# scheme.net
KiCad netlist of a schematic drawn in Altium Designer
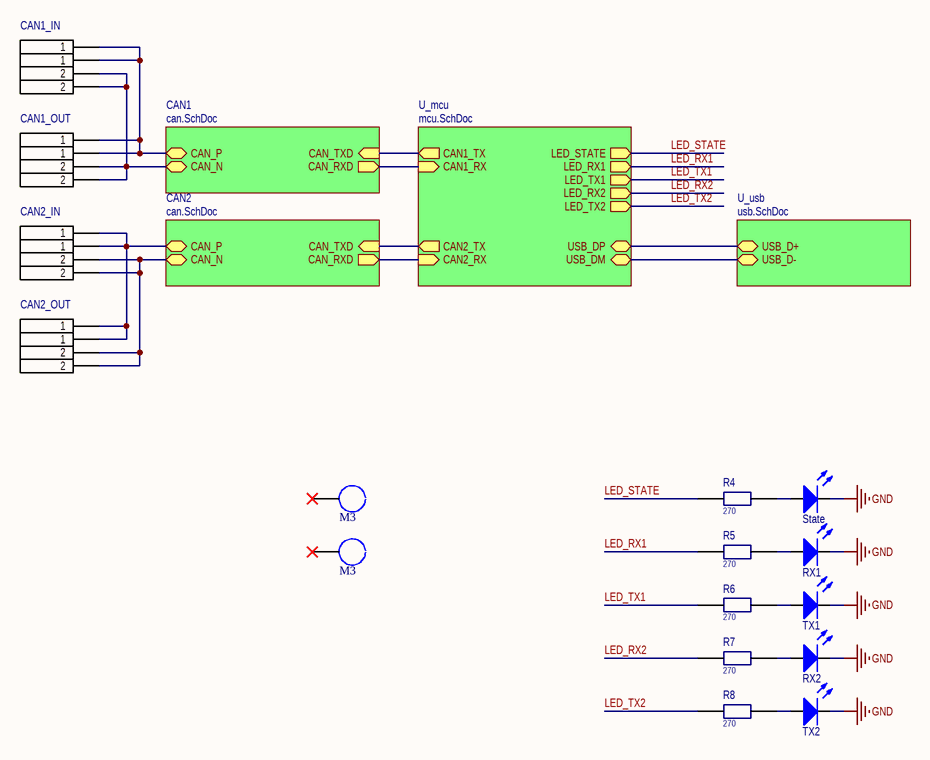
[diagram p0: scheme.SchDoc]

(export (version "E")
  (design (tool "Eeschema 10.0.6"))
  (components
    (comp (ref "*1") (value "M3") (footprint "M3") (libsource (lib "connectors_socets") (part "M3")))
    (comp (ref "*2") (value "M3") (footprint "M3") (libsource (lib "connectors_socets") (part "M3")))
    (comp (ref "CAN1_IN")
      (value "TBLH10-350-02BK")
      (footprint "CUI_TBLH10-350-02BK")
      (fields (field (name "ALTERNATIVE PART") "JILN JL212R-35002B01"))
      (libsource (lib "connectors_socets") (part "TBLH10-350-02BK"))
    )
    (comp (ref "CAN1_OUT")
      (value "TBLH10-350-02BK")
      (footprint "CUI_TBLH10-350-02BK")
      (libsource (lib "connectors_socets") (part "TBLH10-350-02BK"))
    )
    (comp (ref "CAN2_IN")
      (value "TBLH10-350-02BK")
      (footprint "CUI_TBLH10-350-02BK")
      (libsource (lib "connectors_socets") (part "TBLH10-350-02BK"))
    )
    (comp (ref "CAN2_OUT")
      (value "TBLH10-350-02BK")
      (footprint "CUI_TBLH10-350-02BK")
      (libsource (lib "connectors_socets") (part "TBLH10-350-02BK"))
    )
    (comp (ref "R4")
      (value "270")
      (footprint "R_0603")
      (description "Resistor")
      (fields (field (name "PART NUMBER") "RC0603FR-07270RL"))
      (libsource (lib "resistors") (part "RES_SMD"))
    )
    (comp (ref "R5")
      (value "270")
      (footprint "R_0603")
      (description "Resistor")
      (fields (field (name "PART NUMBER") "RC0603FR-07270RL"))
      (libsource (lib "resistors") (part "RES_SMD"))
    )
    (comp (ref "R6")
      (value "270")
      (footprint "R_0603")
      (description "Resistor")
      (fields (field (name "PART NUMBER") "RC0603FR-07270RL"))
      (libsource (lib "resistors") (part "RES_SMD"))
    )
    (comp (ref "R7")
      (value "270")
      (footprint "R_0603")
      (description "Resistor")
      (fields (field (name "PART NUMBER") "RC0603FR-07270RL"))
      (libsource (lib "resistors") (part "RES_SMD"))
    )
    (comp (ref "R8")
      (value "270")
      (footprint "R_0603")
      (description "Resistor")
      (fields (field (name "PART NUMBER") "RC0603FR-07270RL"))
      (libsource (lib "resistors") (part "RES_SMD"))
    )
    (comp (ref "RX1")
      (value "Red")
      (footprint "LED_0603")
      (description "LED")
      (fields (field (name "PART NUMBER") "GNL-0603SGC"))
      (libsource (lib "led_lcd") (part "LED_SMT_0603"))
    )
    (comp (ref "RX2")
      (value "Red")
      (footprint "LED_0603")
      (description "LED")
      (fields (field (name "PART NUMBER") "GNL-0603SGC"))
      (libsource (lib "led_lcd") (part "LED_SMT_0603"))
    )
    (comp (ref "State")
      (value "Red")
      (footprint "LED_0603")
      (description "LED")
      (fields (field (name "PART NUMBER") "GNL-0603SRC"))
      (libsource (lib "led_lcd") (part "LED_SMT_0603"))
    )
    (comp (ref "TX1")
      (value "Red")
      (footprint "LED_0603")
      (description "LED")
      (fields (field (name "PART NUMBER") "GNL-0603SBC"))
      (libsource (lib "led_lcd") (part "LED_SMT_0603"))
    )
    (comp (ref "TX2")
      (value "Red")
      (footprint "LED_0603")
      (description "LED")
      (fields (field (name "PART NUMBER") "GNL-0603SBC"))
      (libsource (lib "led_lcd") (part "LED_SMT_0603"))
    )
  )
  (nets
    (net (code "3") (name "/CAN_N") (class "Default")
      (node (ref "CAN1_IN") (pin "2_A") (pinfunction "2_2_A") (pintype "passive"))
      (node (ref "CAN1_IN") (pin "2_B") (pinfunction "2_2_B") (pintype "passive"))
      (node (ref "CAN1_OUT") (pin "2_A") (pinfunction "2_2_A") (pintype "passive"))
      (node (ref "CAN1_OUT") (pin "2_B") (pinfunction "2_2_B") (pintype "passive"))
    )
    (net (code "4") (name "/CAN_N_1") (class "Default")
      (node (ref "CAN2_IN") (pin "2_A") (pinfunction "2_2_A") (pintype "passive"))
      (node (ref "CAN2_IN") (pin "2_B") (pinfunction "2_2_B") (pintype "passive"))
      (node (ref "CAN2_OUT") (pin "2_A") (pinfunction "2_2_A") (pintype "passive"))
      (node (ref "CAN2_OUT") (pin "2_B") (pinfunction "2_2_B") (pintype "passive"))
    )
    (net (code "5") (name "/CAN_P") (class "Default")
      (node (ref "CAN1_IN") (pin "1_A") (pinfunction "1_1_A") (pintype "passive"))
      (node (ref "CAN1_IN") (pin "1_B") (pinfunction "1_1_B") (pintype "passive"))
      (node (ref "CAN1_OUT") (pin "1_A") (pinfunction "1_1_A") (pintype "passive"))
      (node (ref "CAN1_OUT") (pin "1_B") (pinfunction "1_1_B") (pintype "passive"))
    )
    (net (code "6") (name "/CAN_P_1") (class "Default")
      (node (ref "CAN2_IN") (pin "1_A") (pinfunction "1_1_A") (pintype "passive"))
      (node (ref "CAN2_IN") (pin "1_B") (pinfunction "1_1_B") (pintype "passive"))
      (node (ref "CAN2_OUT") (pin "1_A") (pinfunction "1_1_A") (pintype "passive"))
      (node (ref "CAN2_OUT") (pin "1_B") (pinfunction "1_1_B") (pintype "passive"))
    )
    (net (code "9") (name "/LED_RX1") (class "Default")
      (node (ref "R5") (pin "2") (pinfunction "2_2") (pintype "passive"))
    )
    (net (code "10") (name "/LED_RX2") (class "Default")
      (node (ref "R7") (pin "2") (pinfunction "2_2") (pintype "passive"))
    )
    (net (code "11") (name "/LED_STATE") (class "Default")
      (node (ref "R4") (pin "2") (pinfunction "2_2") (pintype "passive"))
    )
    (net (code "12") (name "/LED_TX1") (class "Default")
      (node (ref "R6") (pin "2") (pinfunction "2_2") (pintype "passive"))
    )
    (net (code "13") (name "/LED_TX2") (class "Default")
      (node (ref "R8") (pin "2") (pinfunction "2_2") (pintype "passive"))
    )
    (net (code "16") (name "GND") (class "Default")
      (node (ref "RX1") (pin "2") (pinfunction "K_2") (pintype "passive"))
      (node (ref "RX2") (pin "2") (pinfunction "K_2") (pintype "passive"))
      (node (ref "State") (pin "2") (pinfunction "K_2") (pintype "passive"))
      (node (ref "TX1") (pin "2") (pinfunction "K_2") (pintype "passive"))
      (node (ref "TX2") (pin "2") (pinfunction "K_2") (pintype "passive"))
    )
    (net (code "17") (name "Net-(RX1-A)") (class "Default")
      (node (ref "R5") (pin "1") (pinfunction "1_1") (pintype "passive"))
      (node (ref "RX1") (pin "1") (pinfunction "A_1") (pintype "passive"))
    )
    (net (code "18") (name "Net-(RX2-A)") (class "Default")
      (node (ref "R7") (pin "1") (pinfunction "1_1") (pintype "passive"))
      (node (ref "RX2") (pin "1") (pinfunction "A_1") (pintype "passive"))
    )
    (net (code "19") (name "Net-(State-A)") (class "Default")
      (node (ref "R4") (pin "1") (pinfunction "1_1") (pintype "passive"))
      (node (ref "State") (pin "1") (pinfunction "A_1") (pintype "passive"))
    )
    (net (code "20") (name "Net-(TX1-A)") (class "Default")
      (node (ref "R6") (pin "1") (pinfunction "1_1") (pintype "passive"))
      (node (ref "TX1") (pin "1") (pinfunction "A_1") (pintype "passive"))
    )
    (net (code "21") (name "Net-(TX2-A)") (class "Default")
      (node (ref "R8") (pin "1") (pinfunction "1_1") (pintype "passive"))
      (node (ref "TX2") (pin "1") (pinfunction "A_1") (pintype "passive"))
    )
    (net (code "22") (name "unconnected-(*1-Pad1)") (class "Default")
      (node (ref "*1") (pin "1") (pinfunction "1_1") (pintype "passive+no_connect"))
    )
    (net (code "23") (name "unconnected-(*2-Pad1)") (class "Default")
      (node (ref "*2") (pin "1") (pinfunction "1_1") (pintype "passive+no_connect"))
    )
  )
)
